# Power.net
KiCad netlist of a schematic drawn in Altium Designer
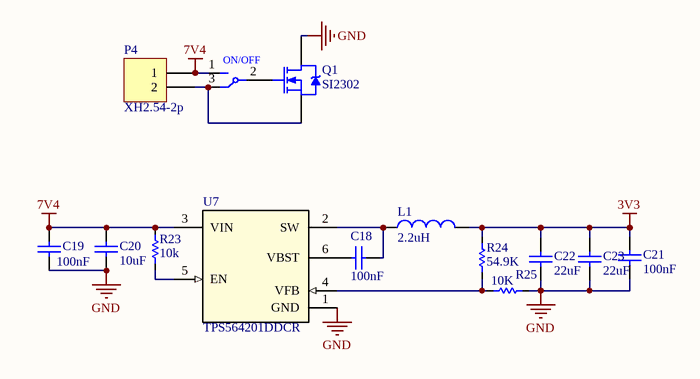
[diagram p0: Power.SchDoc]

(export (version "E")
  (design (tool "Eeschema 10.0.6"))
  (components
    (comp (ref "C18")
      (value "100nF")
      (footprint "0603C")
      (description "Capacitor")
      (fields (field (name "PUBLISHER") "Altium Limited"))
      (libsource (lib "MyComoonents") (part "Cap"))
    )
    (comp (ref "C19")
      (value "100nF")
      (footprint "0603C")
      (description "Capacitor")
      (fields (field (name "PUBLISHER") "Altium Limited"))
      (libsource (lib "MyComoonents") (part "Cap"))
    )
    (comp (ref "C20")
      (value "10uF")
      (footprint "0805")
      (description "Capacitor")
      (fields (field (name "Comment") "1uF/0603/50V") (field (name "PUBLISHER") "Altium Limited"))
      (libsource (lib "OurSuperMiniCar") (part "Cap"))
    )
    (comp (ref "C21")
      (value "100nF")
      (footprint "0603C")
      (description "Capacitor")
      (fields (field (name "PUBLISHER") "Altium Limited"))
      (libsource (lib "MyComoonents") (part "Cap"))
    )
    (comp (ref "C22")
      (value "22uF")
      (footprint "0805")
      (description "Capacitor")
      (fields (field (name "Comment") "1uF/0603/50V") (field (name "PUBLISHER") "Altium Limited"))
      (libsource (lib "OurSuperMiniCar") (part "Cap"))
    )
    (comp (ref "C23")
      (value "22uF")
      (footprint "0805")
      (description "Capacitor")
      (fields (field (name "Comment") "1uF/0603/50V") (field (name "PUBLISHER") "Altium Limited"))
      (libsource (lib "OurSuperMiniCar") (part "Cap"))
    )
    (comp (ref "L1")
      (value "2.2uH")
      (footprint "4020L")
      (description "Inductor")
      (fields (field (name "PUBLISHER") "Altium Limited"))
      (libsource (lib "OurSuperMiniCar") (part "Inductor"))
    )
    (comp (ref "P4")
      (value "XH2.54-2p")
      (footprint "XH-2A")
      (description "Header, 2-Pin")
      (fields (field (name "PUBLISHER") "Altium Limited"))
      (libsource (lib "Miscellaneous Connectors") (part "Header 2"))
    )
    (comp (ref "Q1")
      (value "SI2302")
      (footprint "SOT-23")
      (description "N-Channel Power MOSFET")
      (fields (field (name "PUBLISHER") "Altium Limited"))
      (libsource (lib "OurSuperMiniCar") (part "NMOS_3p"))
    )
    (comp (ref "R23")
      (value "10k")
      (footprint "0603R")
      (description "Resistor")
      (fields (field (name "PUBLISHER") "Altium Limited"))
      (libsource (lib "MyComoonents") (part "Res1"))
    )
    (comp (ref "R24")
      (value "54.9K")
      (footprint "0603R")
      (description "Resistor")
      (fields (field (name "PUBLISHER") "Altium Limited"))
      (libsource (lib "MyComoonents") (part "Res1"))
    )
    (comp (ref "R25")
      (value "10K")
      (footprint "0603R")
      (description "Resistor")
      (fields (field (name "Comment") "1K") (field (name "PUBLISHER") "Altium Limited"))
      (libsource (lib "MyComoonents") (part "Res1"))
    )
    (comp (ref "S2")
      (value "slide switch")
      (footprint "Slide Switch")
      (libsource (lib "OurSuperMiniCar") (part "slide switch"))
    )
    (comp (ref "U7")
      (value "TPS564201DDCR")
      (footprint "SOT-23thin_L")
      (description "Imported")
      (fields (field (name "MANUFACTURER") "Texas Instruments"))
      (libsource (lib "OurSuperMiniCar") (part "TPS564201DDCR"))
    )
  )
  (nets
    (net (code "1") (name "3V3") (class "Default")
      (node (ref "C21") (pin "2") (pinfunction "2_2") (pintype "passive"))
      (node (ref "C22") (pin "2") (pinfunction "2_2") (pintype "passive"))
      (node (ref "C23") (pin "2") (pinfunction "2_2") (pintype "passive"))
      (node (ref "L1") (pin "2") (pinfunction "2_2") (pintype "passive"))
      (node (ref "R24") (pin "2") (pinfunction "2_2") (pintype "passive"))
    )
    (net (code "2") (name "7V4") (class "Default")
      (node (ref "C19") (pin "1") (pinfunction "1_1") (pintype "passive"))
      (node (ref "C20") (pin "2") (pinfunction "2_2") (pintype "passive"))
      (node (ref "P4") (pin "1") (pinfunction "1_1") (pintype "passive"))
      (node (ref "R23") (pin "2") (pinfunction "2_2") (pintype "passive"))
      (node (ref "S2") (pin "1") (pinfunction "NX_1") (pintype "open_collector"))
      (node (ref "U7") (pin "3") (pinfunction "VIN_3") (pintype "power_in"))
    )
    (net (code "3") (name "GND") (class "Default")
      (node (ref "C19") (pin "2") (pinfunction "2_2") (pintype "passive"))
      (node (ref "C20") (pin "1") (pinfunction "1_1") (pintype "passive"))
      (node (ref "C21") (pin "1") (pinfunction "1_1") (pintype "passive"))
      (node (ref "C22") (pin "1") (pinfunction "1_1") (pintype "passive"))
      (node (ref "C23") (pin "1") (pinfunction "1_1") (pintype "passive"))
      (node (ref "Q1") (pin "3") (pinfunction "D_3") (pintype "passive"))
      (node (ref "R25") (pin "1") (pinfunction "1_1") (pintype "passive"))
      (node (ref "U7") (pin "1") (pinfunction "GND_1") (pintype "power_in"))
    )
    (net (code "4") (name "Net-(Q1-G)") (class "Default")
      (node (ref "Q1") (pin "1") (pinfunction "G_1") (pintype "passive"))
      (node (ref "S2") (pin "2") (pinfunction "COM_2") (pintype "open_collector"))
    )
    (net (code "5") (name "Net-(Q1-S)") (class "Default")
      (node (ref "P4") (pin "2") (pinfunction "2_2") (pintype "passive"))
      (node (ref "Q1") (pin "2") (pinfunction "S_2") (pintype "passive"))
      (node (ref "S2") (pin "3") (pinfunction "NC_3") (pintype "open_collector"))
    )
    (net (code "6") (name "Net-(U7-EN)") (class "Default")
      (node (ref "R23") (pin "1") (pinfunction "1_1") (pintype "passive"))
      (node (ref "U7") (pin "5") (pinfunction "EN_5") (pintype "input"))
    )
    (net (code "7") (name "Net-(U7-SW)") (class "Default")
      (node (ref "C18") (pin "2") (pinfunction "2_2") (pintype "passive"))
      (node (ref "L1") (pin "1") (pinfunction "1_1") (pintype "passive"))
      (node (ref "U7") (pin "2") (pinfunction "SW_2") (pintype "power_in"))
    )
    (net (code "8") (name "Net-(U7-VBST)") (class "Default")
      (node (ref "C18") (pin "1") (pinfunction "1_1") (pintype "passive"))
      (node (ref "U7") (pin "6") (pinfunction "VBST_6") (pintype "power_in"))
    )
    (net (code "9") (name "Net-(U7-VFB)") (class "Default")
      (node (ref "R24") (pin "1") (pinfunction "1_1") (pintype "passive"))
      (node (ref "R25") (pin "2") (pinfunction "2_2") (pintype "passive"))
      (node (ref "U7") (pin "4") (pinfunction "VFB_4") (pintype "input"))
    )
  )
)
